# SixPotatoeV5.net
KiCad netlist of a schematic drawn in EAGLE
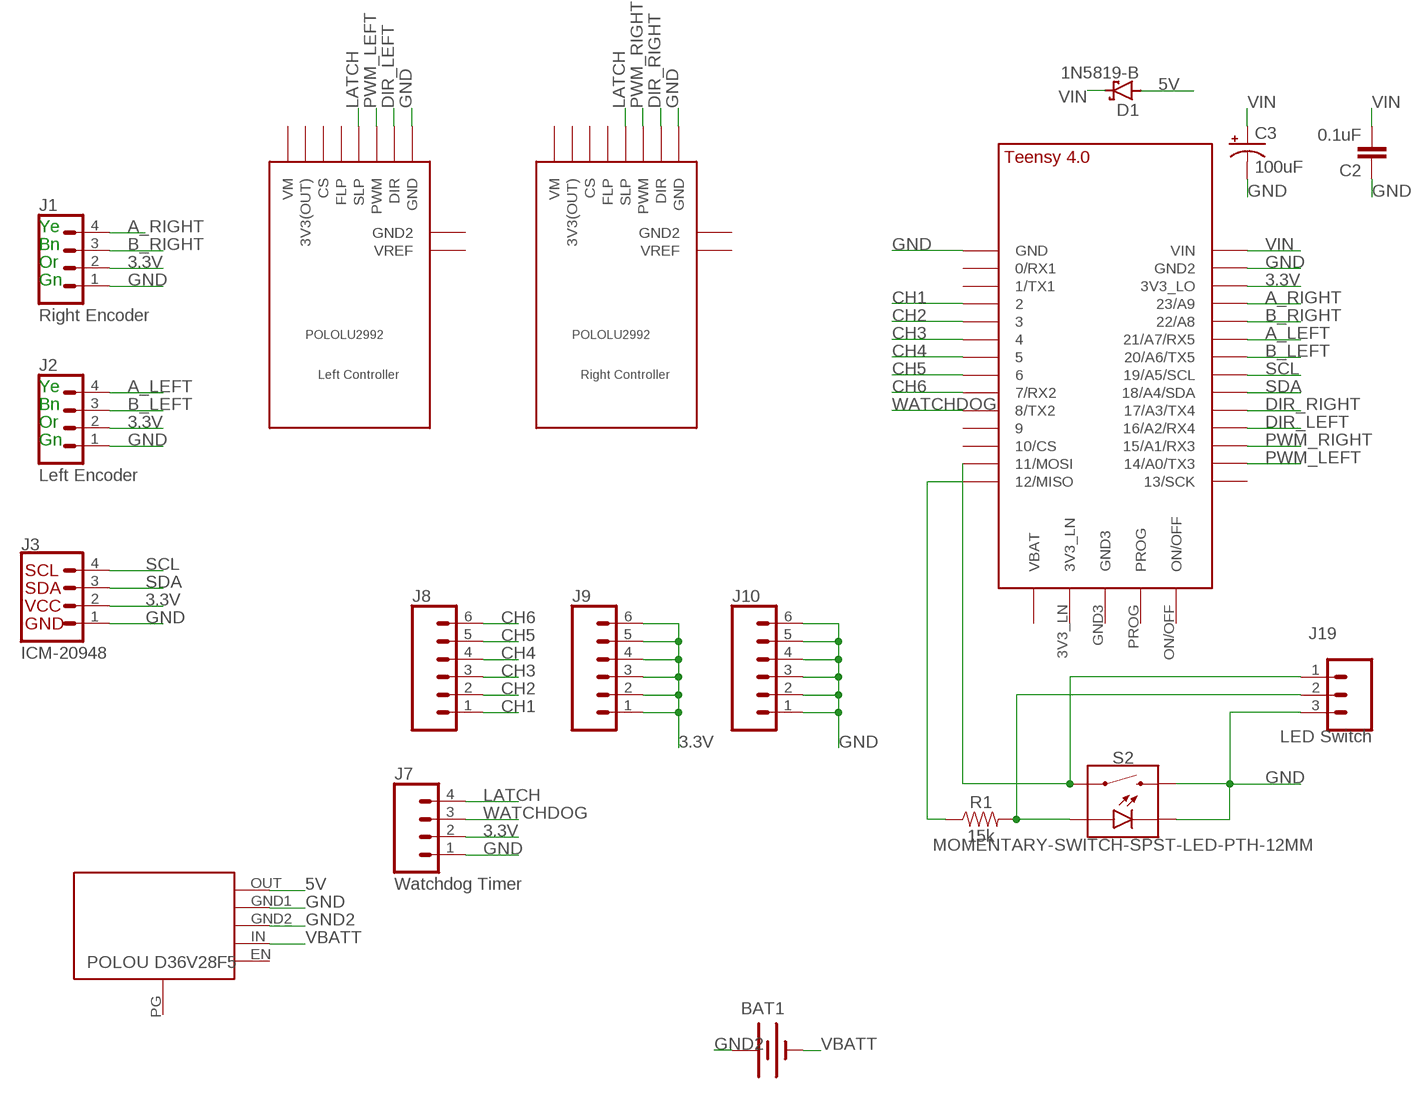
[diagram p0: schematic, sheet 1]

(export (version "E")
  (design (tool "Eeschema 10.0.6"))
  (components
    (comp (ref "BAT1")
      (value "XT60_MALE")
      (footprint "eagle-import:XT60")
      (libsource (lib "eagle-import") (part "XT60_MALE"))
    )
    (comp (ref "C2")
      (value "0.1uF")
      (footprint "eagle-import:CAP-PTH-SMALL-KIT")
      (libsource (lib "eagle-import") (part "0.1UF-KIT-EZ-50V-20%"))
    )
    (comp (ref "C3")
      (value "100uF")
      (footprint "eagle-import:CPOL-RADIAL-2.5MM-6.5MM")
      (libsource (lib "eagle-import") (part "100UF-POLAR-RADIAL-2.5MM-25V-20%"))
    )
    (comp (ref "D1")
      (value "1N5819-B")
      (footprint "eagle-import:DO41-7.6")
      (libsource (lib "eagle-import") (part "1N5819-B"))
    )
    (comp (ref "J1")
      (value "CONN_04")
      (footprint "eagle-import:1X04")
      (fields (field (name "ID") "Right Encoder"))
      (libsource (lib "eagle-import") (part "CONN_04"))
    )
    (comp (ref "J2")
      (value "CONN_04")
      (footprint "eagle-import:1X04")
      (fields (field (name "ID") "Left Encoder"))
      (libsource (lib "eagle-import") (part "CONN_04"))
    )
    (comp (ref "J3")
      (value "I2C_STANDARD")
      (footprint "eagle-import:1X04")
      (fields (field (name "ID") "ICM-20948"))
      (libsource (lib "eagle-import") (part "I2C_STANDARD"))
    )
    (comp (ref "J7")
      (value "CONN_04")
      (footprint "eagle-import:1X04")
      (fields (field (name "ID") "Watchdog Timer"))
      (libsource (lib "eagle-import") (part "CONN_04"))
    )
    (comp (ref "J8")
      (value "CONN_06NO_SILK_FEMALE_PTH")
      (footprint "eagle-import:1X06_NO_SILK")
      (libsource (lib "eagle-import") (part "CONN_06NO_SILK_FEMALE_PTH"))
    )
    (comp (ref "J9")
      (value "CONN_06NO_SILK_FEMALE_PTH")
      (footprint "eagle-import:1X06_NO_SILK")
      (libsource (lib "eagle-import") (part "CONN_06NO_SILK_FEMALE_PTH"))
    )
    (comp (ref "J10")
      (value "CONN_06NO_SILK_FEMALE_PTH")
      (footprint "eagle-import:1X06_NO_SILK")
      (libsource (lib "eagle-import") (part "CONN_06NO_SILK_FEMALE_PTH"))
    )
    (comp (ref "J19")
      (value "CONN_03")
      (footprint "eagle-import:1X03")
      (fields (field (name "ID") "LED Switch"))
      (libsource (lib "eagle-import") (part "CONN_03"))
    )
    (comp (ref "R1")
      (value "15k")
      (footprint "eagle-import:AXIAL-0.3")
      (libsource (lib "eagle-import") (part "15KOHM-HORIZ-1/4W-5%"))
    )
    (comp (ref "S2")
      (value "MOMENTARY-SWITCH-SPST-LED-PTH-12MM")
      (footprint "eagle-import:TACTILE_SWITCH_LED_PTH_12MM")
      (libsource (lib "eagle-import") (part "MOMENTARY-SWITCH-SPST-LED-PTH-12MM"))
    )
    (comp (ref "U$1")
      (value "TEENSY_4.0")
      (footprint "eagle-import:TEENSY_4.0")
      (libsource (lib "eagle-import") (part "TEENSY_4.0"))
    )
    (comp (ref "U$2")
      (value "Left Controller")
      (footprint "eagle-import:POLOLU2992_2")
      (libsource (lib "eagle-import") (part "POLOLU2992_2"))
    )
    (comp (ref "U$3")
      (value "Right Controller")
      (footprint "eagle-import:POLOLU2992_2")
      (libsource (lib "eagle-import") (part "POLOLU2992_2"))
    )
    (comp (ref "U$4")
      (value "POLOU3782")
      (footprint "eagle-import:POLOU3782")
      (libsource (lib "eagle-import") (part "POLOU3782"))
    )
  )
  (nets
    (net (code "1") (name "/3.3V") (class "Default")
      (node (ref "J1") (pin "2") (pinfunction "2_2") (pintype "passive"))
      (node (ref "J2") (pin "2") (pinfunction "2_2") (pintype "passive"))
      (node (ref "J3") (pin "2") (pinfunction "2_2") (pintype "power_in"))
      (node (ref "J7") (pin "2") (pinfunction "2_2") (pintype "passive"))
      (node (ref "J9") (pin "1") (pinfunction "1_1") (pintype "passive"))
      (node (ref "J9") (pin "2") (pinfunction "2_2") (pintype "passive"))
      (node (ref "J9") (pin "3") (pinfunction "3_3") (pintype "passive"))
      (node (ref "J9") (pin "4") (pinfunction "4_4") (pintype "passive"))
      (node (ref "J9") (pin "5") (pinfunction "5_5") (pintype "passive"))
      (node (ref "J9") (pin "6") (pinfunction "6_6") (pintype "passive"))
      (node (ref "U$1") (pin "3V3_LO") (pinfunction "3V3_LO_3V3_LO") (pintype "bidirectional"))
    )
    (net (code "2") (name "/5V") (class "Default")
      (node (ref "D1") (pin "A") (pinfunction "A_A") (pintype "passive"))
      (node (ref "U$4") (pin "OUT") (pinfunction "OUT_OUT") (pintype "bidirectional"))
    )
    (net (code "3") (name "/A_LEFT") (class "Default")
      (node (ref "J2") (pin "4") (pinfunction "4_4") (pintype "passive"))
      (node (ref "U$1") (pin "21/A7") (pinfunction "21/A7/RX5_21/A7") (pintype "bidirectional"))
    )
    (net (code "4") (name "/A_RIGHT") (class "Default")
      (node (ref "J1") (pin "4") (pinfunction "4_4") (pintype "passive"))
      (node (ref "U$1") (pin "23/A9") (pinfunction "23/A9_23/A9") (pintype "bidirectional"))
    )
    (net (code "5") (name "/B_LEFT") (class "Default")
      (node (ref "J2") (pin "3") (pinfunction "3_3") (pintype "passive"))
      (node (ref "U$1") (pin "20/A6") (pinfunction "20/A6/TX5_20/A6") (pintype "bidirectional"))
    )
    (net (code "6") (name "/B_RIGHT") (class "Default")
      (node (ref "J1") (pin "3") (pinfunction "3_3") (pintype "passive"))
      (node (ref "U$1") (pin "22/A8") (pinfunction "22/A8_22/A8") (pintype "bidirectional"))
    )
    (net (code "7") (name "/CH1") (class "Default")
      (node (ref "J8") (pin "1") (pinfunction "1_1") (pintype "passive"))
      (node (ref "U$1") (pin "2") (pinfunction "2_2") (pintype "bidirectional"))
    )
    (net (code "8") (name "/CH2") (class "Default")
      (node (ref "J8") (pin "2") (pinfunction "2_2") (pintype "passive"))
      (node (ref "U$1") (pin "3/CANTX") (pinfunction "3_3/CANTX") (pintype "bidirectional"))
    )
    (net (code "9") (name "/CH3") (class "Default")
      (node (ref "J8") (pin "3") (pinfunction "3_3") (pintype "passive"))
      (node (ref "U$1") (pin "4/CANRX") (pinfunction "4_4/CANRX") (pintype "bidirectional"))
    )
    (net (code "10") (name "/CH4") (class "Default")
      (node (ref "J8") (pin "4") (pinfunction "4_4") (pintype "passive"))
      (node (ref "U$1") (pin "5") (pinfunction "5_5") (pintype "bidirectional"))
    )
    (net (code "11") (name "/CH5") (class "Default")
      (node (ref "J8") (pin "5") (pinfunction "5_5") (pintype "passive"))
      (node (ref "U$1") (pin "6") (pinfunction "6_6") (pintype "bidirectional"))
    )
    (net (code "12") (name "/CH6") (class "Default")
      (node (ref "J8") (pin "6") (pinfunction "6_6") (pintype "passive"))
      (node (ref "U$1") (pin "7") (pinfunction "7/RX2_7") (pintype "bidirectional"))
    )
    (net (code "13") (name "/DIR_LEFT") (class "Default")
      (node (ref "U$1") (pin "16/A2") (pinfunction "16/A2/RX4_16/A2") (pintype "bidirectional"))
      (node (ref "U$2") (pin "DIR") (pinfunction "DIR_DIR") (pintype "bidirectional"))
    )
    (net (code "14") (name "/DIR_RIGHT") (class "Default")
      (node (ref "U$1") (pin "17/A3") (pinfunction "17/A3/TX4_17/A3") (pintype "bidirectional"))
      (node (ref "U$3") (pin "DIR") (pinfunction "DIR_DIR") (pintype "bidirectional"))
    )
    (net (code "15") (name "/GND") (class "Default")
      (node (ref "C2") (pin "1") (pinfunction "1_1") (pintype "passive"))
      (node (ref "C3") (pin "2") (pinfunction "-_2") (pintype "passive"))
      (node (ref "J1") (pin "1") (pinfunction "1_1") (pintype "passive"))
      (node (ref "J10") (pin "1") (pinfunction "1_1") (pintype "passive"))
      (node (ref "J10") (pin "2") (pinfunction "2_2") (pintype "passive"))
      (node (ref "J10") (pin "3") (pinfunction "3_3") (pintype "passive"))
      (node (ref "J10") (pin "4") (pinfunction "4_4") (pintype "passive"))
      (node (ref "J10") (pin "5") (pinfunction "5_5") (pintype "passive"))
      (node (ref "J10") (pin "6") (pinfunction "6_6") (pintype "passive"))
      (node (ref "J19") (pin "3") (pinfunction "3_3") (pintype "passive"))
      (node (ref "J2") (pin "1") (pinfunction "1_1") (pintype "passive"))
      (node (ref "J3") (pin "1") (pinfunction "1_1") (pintype "power_in"))
      (node (ref "J7") (pin "1") (pinfunction "1_1") (pintype "passive"))
      (node (ref "S2") (pin "2") (pinfunction "2_2") (pintype "passive"))
      (node (ref "S2") (pin "C") (pinfunction "C_C") (pintype "passive"))
      (node (ref "U$1") (pin "GND") (pinfunction "GND_GND") (pintype "bidirectional"))
      (node (ref "U$1") (pin "GND2") (pinfunction "GND2_GND2") (pintype "bidirectional"))
      (node (ref "U$2") (pin "GND") (pinfunction "GND_GND") (pintype "bidirectional"))
      (node (ref "U$3") (pin "GND") (pinfunction "GND_GND") (pintype "bidirectional"))
      (node (ref "U$4") (pin "GND1") (pinfunction "GND1_GND1") (pintype "bidirectional"))
    )
    (net (code "16") (name "/GND2") (class "Default")
      (node (ref "BAT1") (pin "+") (pinfunction "+_+") (pintype "power_in"))
      (node (ref "U$4") (pin "GND2") (pinfunction "GND2_GND2") (pintype "bidirectional"))
    )
    (net (code "17") (name "/LATCH") (class "Default")
      (node (ref "J7") (pin "4") (pinfunction "4_4") (pintype "passive"))
      (node (ref "U$2") (pin "SLP") (pinfunction "SLP_SLP") (pintype "bidirectional"))
      (node (ref "U$3") (pin "SLP") (pinfunction "SLP_SLP") (pintype "bidirectional"))
    )
    (net (code "18") (name "/PWM_LEFT") (class "Default")
      (node (ref "U$1") (pin "14/A0") (pinfunction "14/A0/TX3_14/A0") (pintype "bidirectional"))
      (node (ref "U$2") (pin "PWM") (pinfunction "PWM_PWM") (pintype "bidirectional"))
    )
    (net (code "19") (name "/PWM_RIGHT") (class "Default")
      (node (ref "U$1") (pin "15/A1") (pinfunction "15/A1/RX3_15/A1") (pintype "bidirectional"))
      (node (ref "U$3") (pin "PWM") (pinfunction "PWM_PWM") (pintype "bidirectional"))
    )
    (net (code "20") (name "/SCL") (class "Default")
      (node (ref "J3") (pin "4") (pinfunction "4_4") (pintype "passive"))
      (node (ref "U$1") (pin "19/A5/SCL") (pinfunction "19/A5/SCL_19/A5/SCL") (pintype "bidirectional"))
    )
    (net (code "21") (name "/SDA") (class "Default")
      (node (ref "J3") (pin "3") (pinfunction "3_3") (pintype "passive"))
      (node (ref "U$1") (pin "18/A4/SDA") (pinfunction "18/A4/SDA_18/A4/SDA") (pintype "bidirectional"))
    )
    (net (code "22") (name "/VBATT") (class "Default")
      (node (ref "BAT1") (pin "-") (pinfunction "-_-") (pintype "power_in"))
      (node (ref "U$4") (pin "IN") (pinfunction "IN_IN") (pintype "bidirectional"))
    )
    (net (code "23") (name "/VIN") (class "Default")
      (node (ref "C2") (pin "2") (pinfunction "2_2") (pintype "passive"))
      (node (ref "C3") (pin "1") (pinfunction "+_1") (pintype "passive"))
      (node (ref "D1") (pin "C") (pinfunction "C_C") (pintype "passive"))
      (node (ref "U$1") (pin "VIN") (pinfunction "VIN_VIN") (pintype "bidirectional"))
    )
    (net (code "24") (name "/WATCHDOG") (class "Default")
      (node (ref "J7") (pin "3") (pinfunction "3_3") (pintype "passive"))
      (node (ref "U$1") (pin "8") (pinfunction "8/TX2_8") (pintype "bidirectional"))
    )
    (net (code "25") (name "Net-(R1-1)") (class "Default")
      (node (ref "R1") (pin "P$1") (pinfunction "1_P$1") (pintype "passive"))
      (node (ref "U$1") (pin "12/MISO") (pinfunction "12/MISO_12/MISO") (pintype "bidirectional"))
    )
    (net (code "26") (name "Net-(R1-2)") (class "Default")
      (node (ref "J19") (pin "2") (pinfunction "2_2") (pintype "passive"))
      (node (ref "R1") (pin "P$2") (pinfunction "2_P$2") (pintype "passive"))
      (node (ref "S2") (pin "A") (pinfunction "A_A") (pintype "passive"))
    )
    (net (code "27") (name "Net-(S2-1)") (class "Default")
      (node (ref "J19") (pin "1") (pinfunction "1_1") (pintype "passive"))
      (node (ref "S2") (pin "4") (pinfunction "1_4") (pintype "passive"))
      (node (ref "U$1") (pin "11/MOSI") (pinfunction "11/MOSI_11/MOSI") (pintype "bidirectional"))
    )
    (net (code "28") (name "unconnected-(U$1-0{slash}RX1-Pad0{slash}RX)") (class "Default")
      (node (ref "U$1") (pin "0/RX") (pinfunction "0/RX1_0/RX") (pintype "bidirectional"))
    )
    (net (code "29") (name "unconnected-(U$1-1{slash}TX1-Pad1{slash}TX)") (class "Default")
      (node (ref "U$1") (pin "1/TX") (pinfunction "1/TX1_1/TX") (pintype "bidirectional"))
    )
    (net (code "30") (name "unconnected-(U$1-9-Pad9{slash}CS)") (class "Default")
      (node (ref "U$1") (pin "9/CS") (pinfunction "9_9/CS") (pintype "bidirectional"))
    )
    (net (code "31") (name "unconnected-(U$1-Pad3V3_LN)") (class "Default")
      (node (ref "U$1") (pin "3V3_LN") (pinfunction "3V3_LN_3V3_LN") (pintype "bidirectional"))
    )
    (net (code "32") (name "unconnected-(U$1-Pad10{slash}CS)") (class "Default")
      (node (ref "U$1") (pin "10/CS") (pinfunction "10/CS_10/CS") (pintype "bidirectional"))
    )
    (net (code "33") (name "unconnected-(U$1-Pad13{slash}SCK)") (class "Default")
      (node (ref "U$1") (pin "13/SCK") (pinfunction "13/SCK_13/SCK") (pintype "bidirectional"))
    )
    (net (code "34") (name "unconnected-(U$1-PadGND3)") (class "Default")
      (node (ref "U$1") (pin "GND3") (pinfunction "GND3_GND3") (pintype "bidirectional"))
    )
    (net (code "35") (name "unconnected-(U$1-PadON{slash}OFF)") (class "Default")
      (node (ref "U$1") (pin "ON/OFF") (pinfunction "ON/OFF_ON/OFF") (pintype "bidirectional"))
    )
    (net (code "36") (name "unconnected-(U$1-PadPROG)") (class "Default")
      (node (ref "U$1") (pin "PROG") (pinfunction "PROG_PROG") (pintype "bidirectional"))
    )
    (net (code "37") (name "unconnected-(U$1-VBAT-PadVBAT\\)") (class "Default")
      (node (ref "U$1") (pin "VBAT\\") (pinfunction "VBAT_VBAT\\") (pintype "bidirectional"))
    )
    (net (code "38") (name "unconnected-(U$2-Pad3V3(OUT))") (class "Default")
      (node (ref "U$2") (pin "3V3(OUT)") (pinfunction "3V3(OUT)_3V3(OUT)") (pintype "bidirectional"))
    )
    (net (code "39") (name "unconnected-(U$2-PadCS)") (class "Default")
      (node (ref "U$2") (pin "CS") (pinfunction "CS_CS") (pintype "bidirectional"))
    )
    (net (code "40") (name "unconnected-(U$2-PadFLP)") (class "Default")
      (node (ref "U$2") (pin "FLP") (pinfunction "FLP_FLP") (pintype "bidirectional"))
    )
    (net (code "41") (name "unconnected-(U$2-PadGND2)") (class "Default")
      (node (ref "U$2") (pin "GND2") (pinfunction "GND2_GND2") (pintype "bidirectional"))
    )
    (net (code "42") (name "unconnected-(U$2-PadVM)") (class "Default")
      (node (ref "U$2") (pin "VM") (pinfunction "VM_VM") (pintype "bidirectional"))
    )
    (net (code "43") (name "unconnected-(U$2-PadVREF)") (class "Default")
      (node (ref "U$2") (pin "VREF") (pinfunction "VREF_VREF") (pintype "bidirectional"))
    )
    (net (code "44") (name "unconnected-(U$3-Pad3V3(OUT))") (class "Default")
      (node (ref "U$3") (pin "3V3(OUT)") (pinfunction "3V3(OUT)_3V3(OUT)") (pintype "bidirectional"))
    )
    (net (code "45") (name "unconnected-(U$3-PadCS)") (class "Default")
      (node (ref "U$3") (pin "CS") (pinfunction "CS_CS") (pintype "bidirectional"))
    )
    (net (code "46") (name "unconnected-(U$3-PadFLP)") (class "Default")
      (node (ref "U$3") (pin "FLP") (pinfunction "FLP_FLP") (pintype "bidirectional"))
    )
    (net (code "47") (name "unconnected-(U$3-PadGND2)") (class "Default")
      (node (ref "U$3") (pin "GND2") (pinfunction "GND2_GND2") (pintype "bidirectional"))
    )
    (net (code "48") (name "unconnected-(U$3-PadVM)") (class "Default")
      (node (ref "U$3") (pin "VM") (pinfunction "VM_VM") (pintype "bidirectional"))
    )
    (net (code "49") (name "unconnected-(U$3-PadVREF)") (class "Default")
      (node (ref "U$3") (pin "VREF") (pinfunction "VREF_VREF") (pintype "bidirectional"))
    )
    (net (code "50") (name "unconnected-(U$4-PadEN)") (class "Default")
      (node (ref "U$4") (pin "EN") (pinfunction "EN_EN") (pintype "bidirectional"))
    )
    (net (code "51") (name "unconnected-(U$4-PadPG)") (class "Default")
      (node (ref "U$4") (pin "PG") (pinfunction "PG_PG") (pintype "bidirectional"))
    )
  )
)
